# Misc_Periph.net
KiCad netlist of a schematic drawn in Altium Designer
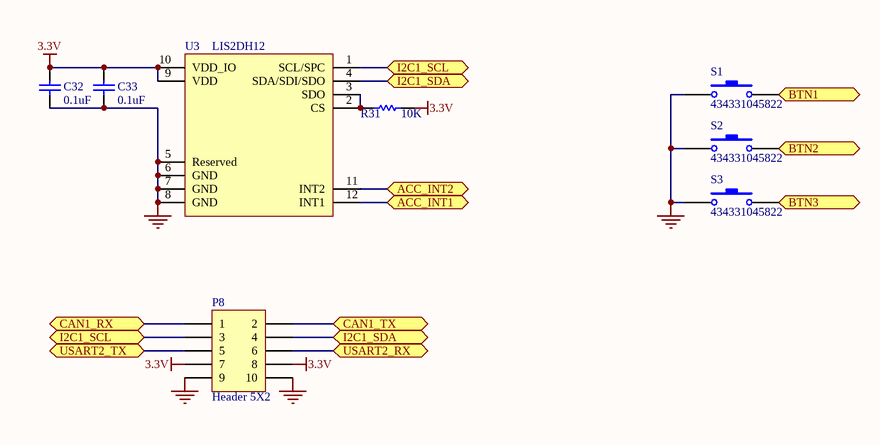
[diagram p0: Misc_Periph.SchDoc]

(export (version "E")
  (design (tool "Eeschema 10.0.6"))
  (components
    (comp (ref "C32")
      (value "0.1uF")
      (footprint "CAPC2012N")
      (description "Capacitor")
      (fields (field (name "Comment") "Cap"))
      (libsource (lib "Core429IBaseBoardVerE") (part "Cap"))
    )
    (comp (ref "C33")
      (value "0.1uF")
      (footprint "CAPC2012N")
      (description "Capacitor")
      (fields (field (name "Comment") "Cap"))
      (libsource (lib "Core429IBaseBoardVerE") (part "Cap"))
    )
    (comp (ref "P8")
      (value "Header 5X2")
      (footprint "HDR2X5")
      (description "Header, 5-Pin, Dual row")
      (libsource (lib "Core429IBaseBoardVerE") (part "Header 5X2"))
    )
    (comp (ref "R31")
      (value "10K")
      (footprint "RESC2012N")
      (description "Resistor")
      (fields (field (name "Comment") "1206"))
      (libsource (lib "Core429IBaseBoard") (part "Res"))
    )
    (comp (ref "S1")
      (value "434331045822")
      (footprint "434331045822")
      (description "Momentary Push Button")
      (libsource (lib "Core429IBaseBoardVerE") (part "SW-PB"))
    )
    (comp (ref "S2")
      (value "434331045822")
      (footprint "434331045822")
      (description "Momentary Push Button")
      (libsource (lib "Core429IBaseBoardVerE") (part "SW-PB"))
    )
    (comp (ref "S3")
      (value "434331045822")
      (footprint "434331045822")
      (description "Momentary Push Button")
      (libsource (lib "Core429IBaseBoardVerE") (part "SW-PB"))
    )
    (comp (ref "U3")
      (value "LIS2DH12")
      (footprint "LGA12C50P4X4_200X200X100")
      (description "MEMS digital output motion sensor ultra-low-power high-performance 3-axis \"femto\" accelerometer")
      (libsource (lib "Core429IBaseBoardVerE") (part "LIS2DH12"))
    )
  )
  (nets
    (net (code "1") (name "/ACC_INT1") (class "Default")
      (node (ref "U3") (pin "12") (pinfunction "INT1_12") (pintype "passive"))
    )
    (net (code "2") (name "/ACC_INT2") (class "Default")
      (node (ref "U3") (pin "11") (pinfunction "INT2_11") (pintype "passive"))
    )
    (net (code "3") (name "/BTN1") (class "Default")
      (node (ref "S1") (pin "2") (pinfunction "2_2") (pintype "passive"))
    )
    (net (code "4") (name "/BTN2") (class "Default")
      (node (ref "S2") (pin "2") (pinfunction "2_2") (pintype "passive"))
    )
    (net (code "5") (name "/BTN3") (class "Default")
      (node (ref "S3") (pin "2") (pinfunction "2_2") (pintype "passive"))
    )
    (net (code "6") (name "/CAN1_RX") (class "Default")
      (node (ref "P8") (pin "1") (pinfunction "1_1") (pintype "passive"))
    )
    (net (code "7") (name "/CAN1_TX") (class "Default")
      (node (ref "P8") (pin "2") (pinfunction "2_2") (pintype "passive"))
    )
    (net (code "8") (name "/I2C1_SCL") (class "Default")
      (node (ref "P8") (pin "3") (pinfunction "3_3") (pintype "passive"))
      (node (ref "U3") (pin "1") (pinfunction "SCL/SPC_1") (pintype "passive"))
    )
    (net (code "9") (name "/I2C1_SDA") (class "Default")
      (node (ref "P8") (pin "4") (pinfunction "4_4") (pintype "passive"))
      (node (ref "U3") (pin "4") (pinfunction "SDA/SDI/SDO_4") (pintype "passive"))
    )
    (net (code "10") (name "/USART2_RX") (class "Default")
      (node (ref "P8") (pin "6") (pinfunction "6_6") (pintype "passive"))
    )
    (net (code "11") (name "/USART2_TX") (class "Default")
      (node (ref "P8") (pin "5") (pinfunction "5_5") (pintype "passive"))
    )
    (net (code "12") (name "3.3V") (class "Default")
      (node (ref "C32") (pin "2") (pinfunction "2_2") (pintype "passive"))
      (node (ref "C33") (pin "2") (pinfunction "2_2") (pintype "passive"))
      (node (ref "P8") (pin "7") (pinfunction "7_7") (pintype "passive"))
      (node (ref "P8") (pin "8") (pinfunction "8_8") (pintype "passive"))
      (node (ref "R31") (pin "1") (pinfunction "1_1") (pintype "passive"))
      (node (ref "U3") (pin "10") (pinfunction "VDD_IO_10") (pintype "passive"))
      (node (ref "U3") (pin "9") (pinfunction "VDD_9") (pintype "passive"))
    )
    (net (code "13") (name "DGND") (class "Default")
      (node (ref "C32") (pin "1") (pinfunction "1_1") (pintype "passive"))
      (node (ref "C33") (pin "1") (pinfunction "1_1") (pintype "passive"))
      (node (ref "P8") (pin "10") (pinfunction "10_10") (pintype "passive"))
      (node (ref "P8") (pin "9") (pinfunction "9_9") (pintype "passive"))
      (node (ref "S1") (pin "1") (pinfunction "1_1") (pintype "passive"))
      (node (ref "S2") (pin "1") (pinfunction "1_1") (pintype "passive"))
      (node (ref "S3") (pin "1") (pinfunction "1_1") (pintype "passive"))
      (node (ref "U3") (pin "5") (pinfunction "Reserved_5") (pintype "passive"))
      (node (ref "U3") (pin "6") (pinfunction "GND_6") (pintype "passive"))
      (node (ref "U3") (pin "7") (pinfunction "GND_7") (pintype "passive"))
      (node (ref "U3") (pin "8") (pinfunction "GND_8") (pintype "passive"))
    )
    (net (code "14") (name "Net-(U3-CS)") (class "Default")
      (node (ref "R31") (pin "2") (pinfunction "2_2") (pintype "passive"))
      (node (ref "U3") (pin "2") (pinfunction "CS_2") (pintype "passive"))
      (node (ref "U3") (pin "3") (pinfunction "SDO_3") (pintype "passive"))
    )
  )
)
